# openSX70_ALADDIN_V391SEEED_20180205.net
KiCad netlist of a schematic drawn in EAGLE
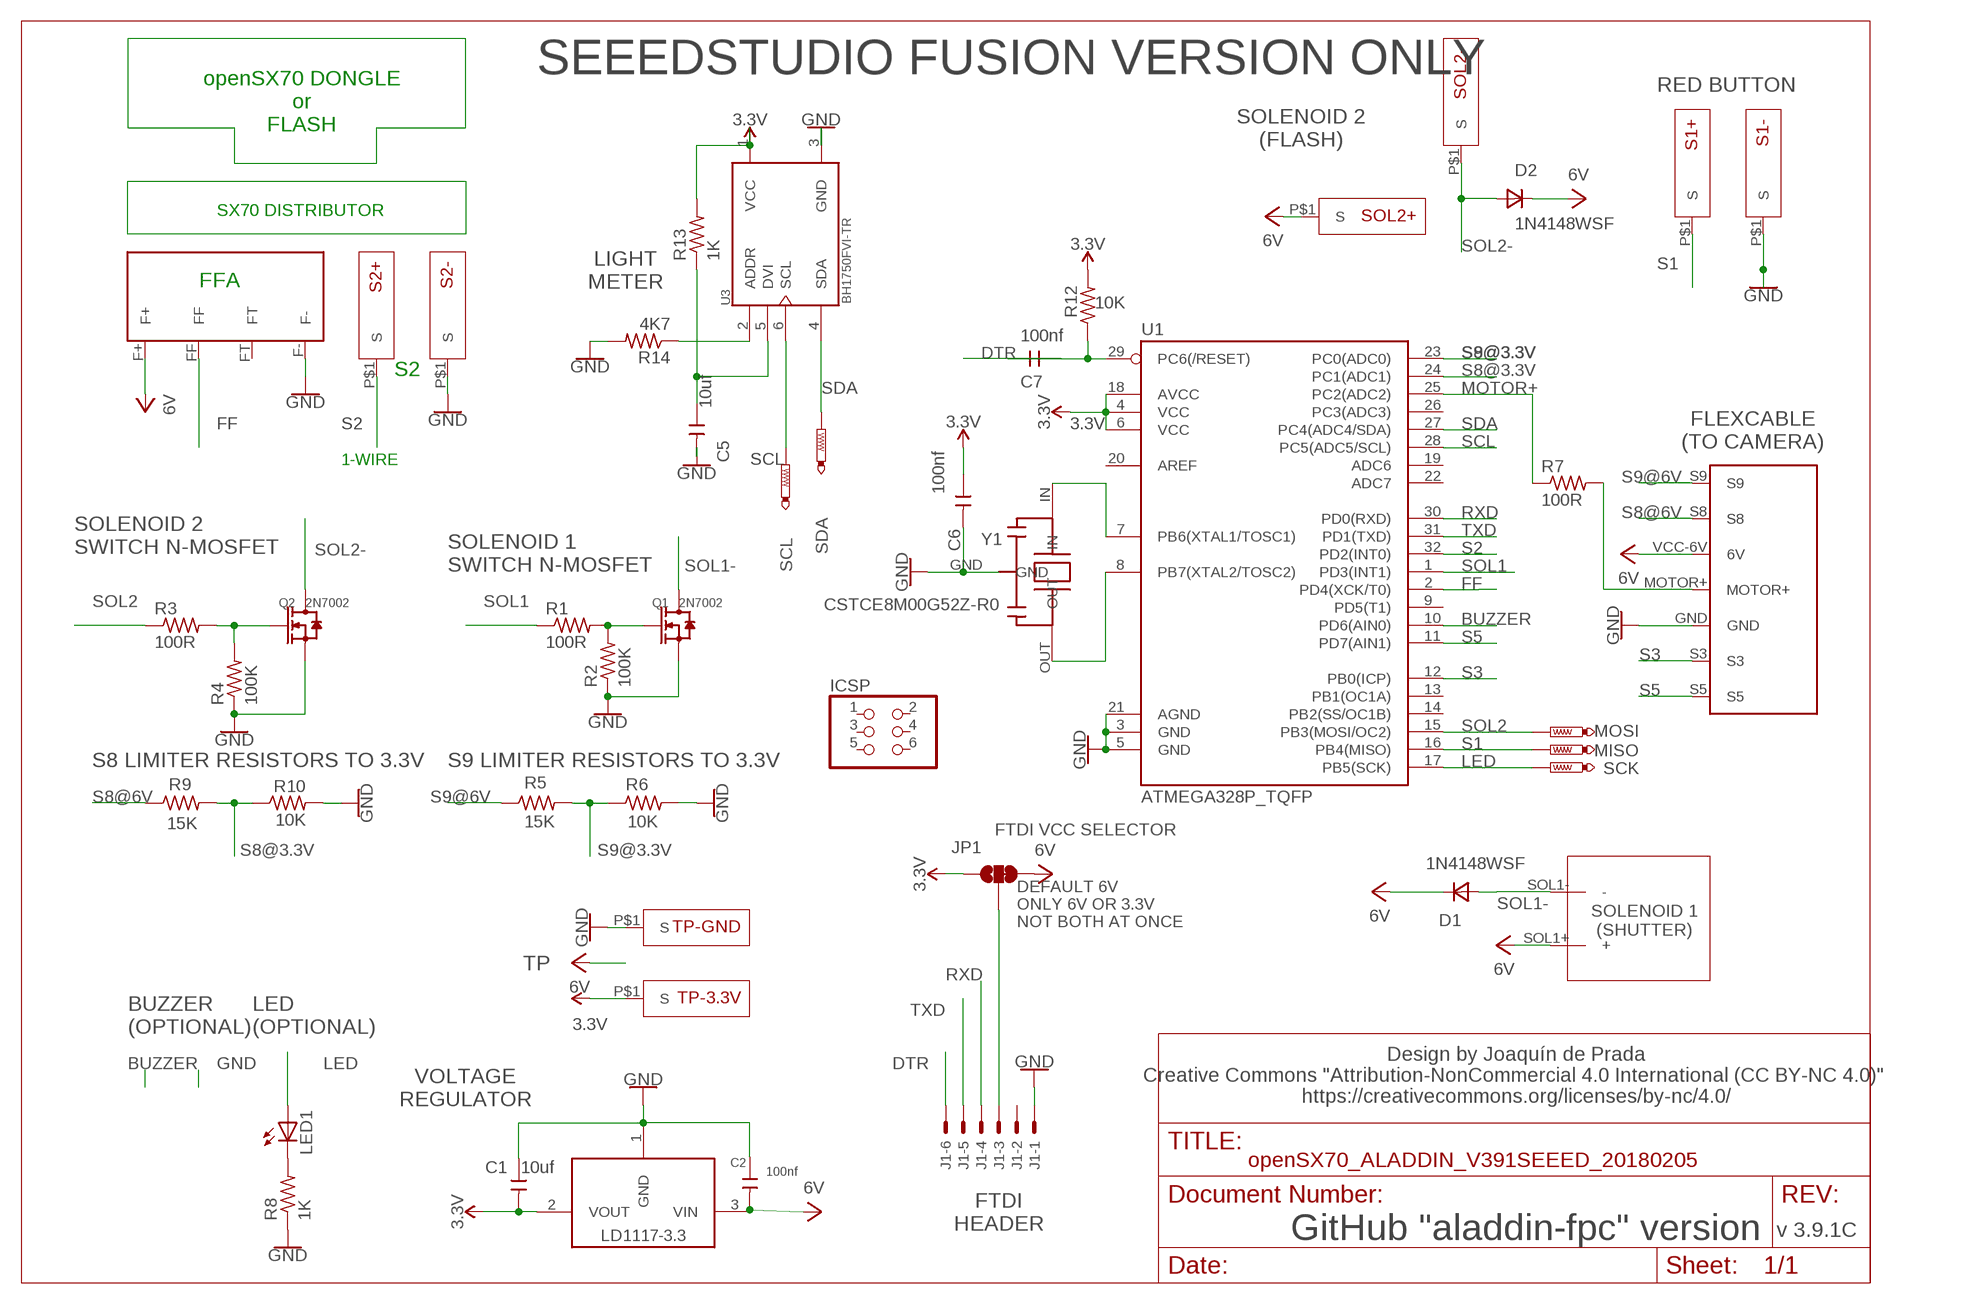
[diagram p0: schematic, sheet 1]

(export (version "E")
  (design (tool "Eeschema 10.0.6"))
  (components
    (comp (ref "C1")
      (value "10uf")
      (footprint "eagle-import:C0603")
      (fields (field (name "MPN") "CC0603KRX5R6BB106"))
      (libsource (lib "eagle-import") (part "CERAMIC-10UF-10V-10%-X5R(0603)"))
    )
    (comp (ref "C2")
      (value "100nf")
      (footprint "eagle-import:C0603")
      (fields (field (name "MPN") "CC0603KRX7R9BB104"))
      (libsource (lib "eagle-import") (part "CERAMIC-100NF-50V-10%-X7R(0603)"))
    )
    (comp (ref "C5")
      (value "10uf")
      (footprint "eagle-import:C0603")
      (fields (field (name "MPN") "CC0603KRX5R6BB106"))
      (libsource (lib "eagle-import") (part "CERAMIC-10UF-10V-10%-X5R(0603)"))
    )
    (comp (ref "C6")
      (value "100nf")
      (footprint "eagle-import:C0603")
      (fields (field (name "MPN") "CC0603KRX7R9BB104"))
      (libsource (lib "eagle-import") (part "CERAMIC-100NF-50V-10%-X7R(0603)"))
    )
    (comp (ref "C7")
      (value "100nf")
      (footprint "eagle-import:C0603")
      (fields (field (name "MPN") "CC0603KRX7R9BB104"))
      (libsource (lib "eagle-import") (part "CERAMIC-100NF-50V-10%-X7R(0603)"))
    )
    (comp (ref "D1")
      (value "1N4148WSF")
      (footprint "eagle-import:SOD323")
      (fields (field (name "MPN") "CDSOD323-T05C"))
      (libsource (lib "eagle-import") (part "DSOD323"))
    )
    (comp (ref "D2")
      (value "1N4148WSF")
      (footprint "eagle-import:SOD323")
      (fields (field (name "MPN") "CDSOD323-T05C"))
      (libsource (lib "eagle-import") (part "DSOD323"))
    )
    (comp (ref "ICSP")
      (value "PINHD-2X3")
      (footprint "eagle-import:2X03")
      (libsource (lib "eagle-import") (part "PINHD-2X3"))
    )
    (comp (ref "J1")
      (value "GND")
      (footprint "eagle-import:XF2L-0625-1")
      (fields (field (name "MF") "OMRON COMPONENTS USA") (field (name "MPN") "XF2L-0625-1"))
      (libsource (lib "eagle-import") (part "XF2-06?25-1L"))
    )
    (comp (ref "JP1")
      (value "FTDI VCC SELECTOR")
      (footprint "eagle-import:SMT-JUMPER_3_1-NC_TRACE_SILK")
      (libsource (lib "eagle-import") (part "JUMPER-SMT_3_1-NC_TRACE_SILK"))
    )
    (comp (ref "LD11172.5V")
      (value "LD1117 2.5V")
      (footprint "eagle-import:SOT223")
      (fields (field (name "MF") "Advanced Monolithic Systems") (field (name "MP") "AMS1117-5.0"))
      (libsource (lib "eagle-import") (part "LD1117-3.3"))
    )
    (comp (ref "LED1")
      (value "LEDCHIPLED_0805")
      (footprint "eagle-import:CHIPLED_0805")
      (libsource (lib "eagle-import") (part "LEDCHIPLED_0805"))
    )
    (comp (ref "MISO")
      (value "PTR1TP08R")
      (footprint "eagle-import:TP08R")
      (libsource (lib "eagle-import") (part "PTR1TP08R"))
    )
    (comp (ref "MOSI")
      (value "PTR1TP08R")
      (footprint "eagle-import:TP08R")
      (libsource (lib "eagle-import") (part "PTR1TP08R"))
    )
    (comp (ref "Q1")
      (value "2N7002")
      (footprint "eagle-import:SOT-23")
      (fields (field (name "MPN") "2N7002,215"))
      (libsource (lib "eagle-import") (part "SMD-MOSFET-N-CH-60V-300MA-LOGIC-LEVEL-FET-2N7002(SOT-23)"))
    )
    (comp (ref "Q2")
      (value "2N7002")
      (footprint "eagle-import:SOT-23")
      (fields (field (name "MPN") "2N7002,215"))
      (libsource (lib "eagle-import") (part "SMD-MOSFET-N-CH-60V-300MA-LOGIC-LEVEL-FET-2N7002(SOT-23)"))
    )
    (comp (ref "R1")
      (value "100R")
      (footprint "eagle-import:R0603")
      (libsource (lib "eagle-import") (part "R-US_R0603"))
    )
    (comp (ref "R2")
      (value "100K")
      (footprint "eagle-import:R0603")
      (libsource (lib "eagle-import") (part "R-US_R0603"))
    )
    (comp (ref "R3")
      (value "100R")
      (footprint "eagle-import:R0603")
      (libsource (lib "eagle-import") (part "R-US_R0603"))
    )
    (comp (ref "R4")
      (value "100K")
      (footprint "eagle-import:R0603")
      (libsource (lib "eagle-import") (part "R-US_R0603"))
    )
    (comp (ref "R5")
      (value "15K")
      (footprint "eagle-import:R0603")
      (libsource (lib "eagle-import") (part "R-US_R0603"))
    )
    (comp (ref "R6")
      (value "10K")
      (footprint "eagle-import:R0603")
      (libsource (lib "eagle-import") (part "R-US_R0603"))
    )
    (comp (ref "R7")
      (value "100R")
      (footprint "eagle-import:R0603")
      (libsource (lib "eagle-import") (part "R-US_R0603"))
    )
    (comp (ref "R8")
      (value "1K")
      (footprint "eagle-import:R0603")
      (libsource (lib "eagle-import") (part "R-US_R0603"))
    )
    (comp (ref "R9")
      (value "15K")
      (footprint "eagle-import:R0603")
      (libsource (lib "eagle-import") (part "R-US_R0603"))
    )
    (comp (ref "R10")
      (value "10K")
      (footprint "eagle-import:R0603")
      (libsource (lib "eagle-import") (part "R-US_R0603"))
    )
    (comp (ref "R12")
      (value "10K")
      (footprint "eagle-import:R0603")
      (libsource (lib "eagle-import") (part "R-US_R0603"))
    )
    (comp (ref "R13")
      (value "1K")
      (footprint "eagle-import:R0603")
      (libsource (lib "eagle-import") (part "R-US_R0603"))
    )
    (comp (ref "R14")
      (value "4K7")
      (footprint "eagle-import:R0603")
      (libsource (lib "eagle-import") (part "R-US_R0603"))
    )
    (comp (ref "S1+")
      (value "SX70-S-PAD-NEW")
      (footprint "eagle-import:SX70-S-PAD2")
      (libsource (lib "eagle-import") (part "SX70-S-PAD-NEW"))
    )
    (comp (ref "S1-")
      (value "SX70-S-PAD-NEW")
      (footprint "eagle-import:SX70-S-PAD2")
      (libsource (lib "eagle-import") (part "SX70-S-PAD-NEW"))
    )
    (comp (ref "S2+")
      (value "SX70-S-PAD-NEW")
      (footprint "eagle-import:SX70-S-PAD2")
      (libsource (lib "eagle-import") (part "SX70-S-PAD-NEW"))
    )
    (comp (ref "S2-")
      (value "SX70-S-PAD-NEW")
      (footprint "eagle-import:SX70-S-PAD2")
      (libsource (lib "eagle-import") (part "SX70-S-PAD-NEW"))
    )
    (comp (ref "SCK")
      (value "PTR1TP08R")
      (footprint "eagle-import:TP08R")
      (libsource (lib "eagle-import") (part "PTR1TP08R"))
    )
    (comp (ref "SCL")
      (value "PTR1TP08R")
      (footprint "eagle-import:TP08R")
      (libsource (lib "eagle-import") (part "PTR1TP08R"))
    )
    (comp (ref "SDA")
      (value "PTR1TP08R")
      (footprint "eagle-import:TP08R")
      (libsource (lib "eagle-import") (part "PTR1TP08R"))
    )
    (comp (ref "SOL1")
      (value "SX70-SOLENOID1-2PADS")
      (footprint "eagle-import:SX70-SOLENOID1-2")
      (libsource (lib "eagle-import") (part "SX70-SOLENOID1-2PADS"))
    )
    (comp (ref "SOL2+")
      (value "SX70-S-PAD-NEW")
      (footprint "eagle-import:SX70-S-PAD2")
      (libsource (lib "eagle-import") (part "SX70-S-PAD-NEW"))
    )
    (comp (ref "SOL2-")
      (value "SX70-S-PAD-NEW")
      (footprint "eagle-import:SX70-S-PAD2")
      (libsource (lib "eagle-import") (part "SX70-S-PAD-NEW"))
    )
    (comp (ref "TP-3.3V")
      (value "SX70-S-PAD-NEW")
      (footprint "eagle-import:SX70-S-PAD2")
      (libsource (lib "eagle-import") (part "SX70-S-PAD-NEW"))
    )
    (comp (ref "TP-GND")
      (value "SX70-S-PAD-NEW")
      (footprint "eagle-import:SX70-S-PAD2")
      (libsource (lib "eagle-import") (part "SX70-S-PAD-NEW"))
    )
    (comp (ref "U$1")
      (value "SX70-7-PAD")
      (footprint "eagle-import:SX70-7-PAD")
      (libsource (lib "eagle-import") (part "SX70-7-PAD"))
    )
    (comp (ref "U$2")
      (value "FFA")
      (footprint "eagle-import:FFA-PAD-PACKAGE")
      (libsource (lib "eagle-import") (part "SX70-FFA-PAD"))
    )
    (comp (ref "U1")
      (value "ATMEGA328P_TQFP")
      (footprint "eagle-import:TQFP32-08")
      (libsource (lib "eagle-import") (part "ATMEGA328P_TQFP"))
    )
    (comp (ref "U3")
      (value "BH1750FVI-TR")
      (footprint "eagle-import:SOTFL50P300X75-6N")
      (fields (field (name "MF") "Rohm"))
      (libsource (lib "eagle-import") (part "BH1750FVI-TR"))
    )
    (comp (ref "Y1")
      (value "CSTCE8M00G52Z-R0")
      (footprint "eagle-import:CFP95P160X100-3N")
      (fields (field (name "MF") "Murata") (field (name "MP") "CSTCE16M0V53-R0"))
      (libsource (lib "eagle-import") (part "CSTCE16M0V53-R0"))
    )
  )
  (nets
    (net (code "1") (name "/BUZZER") (class "Default")
      (node (ref "U1") (pin "10") (pinfunction "PD6(AIN0)_10") (pintype "bidirectional"))
    )
    (net (code "2") (name "/DTR") (class "Default")
      (node (ref "C7") (pin "1") (pinfunction "1_1") (pintype "passive"))
      (node (ref "J1") (pin "6") (pinfunction "MS_6") (pintype "passive"))
    )
    (net (code "3") (name "/FF") (class "Default")
      (node (ref "U$2") (pin "FF") (pinfunction "FF_FF") (pintype "bidirectional"))
      (node (ref "U1") (pin "2") (pinfunction "PD4(XCK/T0)_2") (pintype "bidirectional"))
    )
    (net (code "4") (name "/LED") (class "Default")
      (node (ref "LED1") (pin "A") (pinfunction "A_A") (pintype "passive"))
      (node (ref "SCK") (pin "TP") (pinfunction "TP_TP") (pintype "input"))
      (node (ref "U1") (pin "17") (pinfunction "PB5(SCK)_17") (pintype "bidirectional"))
    )
    (net (code "5") (name "/MOTOR+") (class "Default")
      (node (ref "R7") (pin "1") (pinfunction "1_1") (pintype "passive"))
      (node (ref "U1") (pin "25") (pinfunction "PC2(ADC2)_25") (pintype "bidirectional"))
    )
    (net (code "6") (name "/RXD") (class "Default")
      (node (ref "J1") (pin "4") (pinfunction "MS_4") (pintype "passive"))
      (node (ref "U1") (pin "30") (pinfunction "PD0(RXD)_30") (pintype "bidirectional"))
    )
    (net (code "7") (name "/S1") (class "Default")
      (node (ref "MISO") (pin "TP") (pinfunction "TP_TP") (pintype "input"))
      (node (ref "S1+") (pin "P$1") (pinfunction "S_P$1") (pintype "bidirectional"))
      (node (ref "U1") (pin "16") (pinfunction "PB4(MISO)_16") (pintype "bidirectional"))
    )
    (net (code "8") (name "/S2") (class "Default")
      (node (ref "S2+") (pin "P$1") (pinfunction "S_P$1") (pintype "bidirectional"))
      (node (ref "U1") (pin "32") (pinfunction "PD2(INT0)_32") (pintype "bidirectional"))
    )
    (net (code "9") (name "/S3") (class "Default")
      (node (ref "U$1") (pin "S3") (pinfunction "S3_S3") (pintype "bidirectional"))
      (node (ref "U1") (pin "12") (pinfunction "PB0(ICP)_12") (pintype "bidirectional"))
    )
    (net (code "10") (name "/S5") (class "Default")
      (node (ref "U$1") (pin "S5") (pinfunction "S5_S5") (pintype "bidirectional"))
      (node (ref "U1") (pin "11") (pinfunction "PD7(AIN1)_11") (pintype "bidirectional"))
    )
    (net (code "11") (name "/S8@3.3V") (class "Default")
      (node (ref "R10") (pin "1") (pinfunction "1_1") (pintype "passive"))
      (node (ref "R9") (pin "2") (pinfunction "2_2") (pintype "passive"))
      (node (ref "U1") (pin "24") (pinfunction "PC1(ADC1)_24") (pintype "bidirectional"))
    )
    (net (code "12") (name "/S8@6V") (class "Default")
      (node (ref "R9") (pin "1") (pinfunction "1_1") (pintype "passive"))
      (node (ref "U$1") (pin "S8") (pinfunction "S8_S8") (pintype "bidirectional"))
    )
    (net (code "13") (name "/S9@3.3V") (class "Default")
      (node (ref "R5") (pin "2") (pinfunction "2_2") (pintype "passive"))
      (node (ref "R6") (pin "1") (pinfunction "1_1") (pintype "passive"))
      (node (ref "U1") (pin "23") (pinfunction "PC0(ADC0)_23") (pintype "bidirectional"))
    )
    (net (code "14") (name "/S9@6V") (class "Default")
      (node (ref "R5") (pin "1") (pinfunction "1_1") (pintype "passive"))
      (node (ref "U$1") (pin "S9") (pinfunction "S9_S9") (pintype "bidirectional"))
    )
    (net (code "15") (name "/SCL") (class "Default")
      (node (ref "SCL") (pin "TP") (pinfunction "TP_TP") (pintype "input"))
      (node (ref "U1") (pin "28") (pinfunction "PC5(ADC5/SCL)_28") (pintype "bidirectional"))
      (node (ref "U3") (pin "6") (pinfunction "SCL_6") (pintype "input"))
    )
    (net (code "16") (name "/SDA") (class "Default")
      (node (ref "SDA") (pin "TP") (pinfunction "TP_TP") (pintype "input"))
      (node (ref "U1") (pin "27") (pinfunction "PC4(ADC4/SDA)_27") (pintype "bidirectional"))
      (node (ref "U3") (pin "4") (pinfunction "SDA_4") (pintype "bidirectional"))
    )
    (net (code "17") (name "/SOL1") (class "Default")
      (node (ref "R1") (pin "1") (pinfunction "1_1") (pintype "passive"))
      (node (ref "U1") (pin "1") (pinfunction "PD3(INT1)_1") (pintype "bidirectional"))
    )
    (net (code "18") (name "/SOL1-") (class "Default")
      (node (ref "D1") (pin "2") (pinfunction "A_2") (pintype "passive"))
      (node (ref "Q1") (pin "3") (pinfunction "D_3") (pintype "passive"))
      (node (ref "SOL1") (pin "SOL1-") (pinfunction "-_SOL1-") (pintype "bidirectional"))
    )
    (net (code "19") (name "/SOL2") (class "Default")
      (node (ref "MOSI") (pin "TP") (pinfunction "TP_TP") (pintype "input"))
      (node (ref "R3") (pin "1") (pinfunction "1_1") (pintype "passive"))
      (node (ref "U1") (pin "15") (pinfunction "PB3(MOSI/OC2)_15") (pintype "bidirectional"))
    )
    (net (code "20") (name "/SOL2-") (class "Default")
      (node (ref "D2") (pin "2") (pinfunction "A_2") (pintype "passive"))
      (node (ref "Q2") (pin "3") (pinfunction "D_3") (pintype "passive"))
      (node (ref "SOL2-") (pin "P$1") (pinfunction "S_P$1") (pintype "bidirectional"))
    )
    (net (code "21") (name "/TXD") (class "Default")
      (node (ref "J1") (pin "5") (pinfunction "MS_5") (pintype "passive"))
      (node (ref "U1") (pin "31") (pinfunction "PD1(TXD)_31") (pintype "bidirectional"))
    )
    (net (code "22") (name "3.3V") (class "Default")
      (node (ref "C1") (pin "2") (pinfunction "2_2") (pintype "passive"))
      (node (ref "C6") (pin "1") (pinfunction "1_1") (pintype "passive"))
      (node (ref "JP1") (pin "1") (pinfunction "1_1") (pintype "passive"))
      (node (ref "LD11172.5V") (pin "2") (pinfunction "VOUT_2") (pintype "bidirectional"))
      (node (ref "R12") (pin "2") (pinfunction "2_2") (pintype "passive"))
      (node (ref "R13") (pin "2") (pinfunction "2_2") (pintype "passive"))
      (node (ref "TP-3.3V") (pin "P$1") (pinfunction "S_P$1") (pintype "bidirectional"))
      (node (ref "U1") (pin "18") (pinfunction "AVCC_18") (pintype "bidirectional"))
      (node (ref "U1") (pin "4") (pinfunction "VCC_4") (pintype "bidirectional"))
      (node (ref "U1") (pin "6") (pinfunction "VCC_6") (pintype "bidirectional"))
      (node (ref "U3") (pin "1") (pinfunction "VCC_1") (pintype "power_in"))
    )
    (net (code "23") (name "6V") (class "Default")
      (node (ref "C2") (pin "2") (pinfunction "2_2") (pintype "passive"))
      (node (ref "D1") (pin "1") (pinfunction "C_1") (pintype "passive"))
      (node (ref "D2") (pin "1") (pinfunction "C_1") (pintype "passive"))
      (node (ref "JP1") (pin "3") (pinfunction "3_3") (pintype "passive"))
      (node (ref "LD11172.5V") (pin "3") (pinfunction "VIN_3") (pintype "bidirectional"))
      (node (ref "SOL1") (pin "SOL1+") (pinfunction "+_SOL1+") (pintype "bidirectional"))
      (node (ref "SOL2+") (pin "P$1") (pinfunction "S_P$1") (pintype "bidirectional"))
      (node (ref "U$1") (pin "VCC-6V") (pinfunction "6V_VCC-6V") (pintype "bidirectional"))
      (node (ref "U$2") (pin "F+") (pinfunction "F+_F+") (pintype "bidirectional"))
    )
    (net (code "24") (name "GND") (class "Default")
      (node (ref "C1") (pin "1") (pinfunction "1_1") (pintype "passive"))
      (node (ref "C2") (pin "1") (pinfunction "1_1") (pintype "passive"))
      (node (ref "C5") (pin "2") (pinfunction "2_2") (pintype "passive"))
      (node (ref "C6") (pin "2") (pinfunction "2_2") (pintype "passive"))
      (node (ref "J1") (pin "1") (pinfunction "MS_1") (pintype "passive"))
      (node (ref "LD11172.5V") (pin "1") (pinfunction "GND_1") (pintype "bidirectional"))
      (node (ref "Q1") (pin "2") (pinfunction "S_2") (pintype "passive"))
      (node (ref "Q2") (pin "2") (pinfunction "S_2") (pintype "passive"))
      (node (ref "R10") (pin "2") (pinfunction "2_2") (pintype "passive"))
      (node (ref "R14") (pin "2") (pinfunction "2_2") (pintype "passive"))
      (node (ref "R2") (pin "1") (pinfunction "1_1") (pintype "passive"))
      (node (ref "R4") (pin "1") (pinfunction "1_1") (pintype "passive"))
      (node (ref "R6") (pin "2") (pinfunction "2_2") (pintype "passive"))
      (node (ref "R8") (pin "1") (pinfunction "1_1") (pintype "passive"))
      (node (ref "S1-") (pin "P$1") (pinfunction "S_P$1") (pintype "bidirectional"))
      (node (ref "S2-") (pin "P$1") (pinfunction "S_P$1") (pintype "bidirectional"))
      (node (ref "TP-GND") (pin "P$1") (pinfunction "S_P$1") (pintype "bidirectional"))
      (node (ref "U$1") (pin "GND") (pinfunction "GND_GND") (pintype "bidirectional"))
      (node (ref "U$2") (pin "F-") (pinfunction "F-_F-") (pintype "bidirectional"))
      (node (ref "U1") (pin "21") (pinfunction "AGND_21") (pintype "bidirectional"))
      (node (ref "U1") (pin "3") (pinfunction "GND_3") (pintype "bidirectional"))
      (node (ref "U1") (pin "5") (pinfunction "GND_5") (pintype "bidirectional"))
      (node (ref "U3") (pin "3") (pinfunction "GND_3") (pintype "power_in"))
      (node (ref "Y1") (pin "GND") (pinfunction "GND_GND") (pintype "passive"))
    )
    (net (code "25") (name "Net-(J1C-MS)") (class "Default")
      (node (ref "J1") (pin "3") (pinfunction "MS_3") (pintype "passive"))
      (node (ref "JP1") (pin "2") (pinfunction "2_2") (pintype "passive"))
    )
    (net (code "26") (name "Net-(LED1-PadC)") (class "Default")
      (node (ref "LED1") (pin "C") (pinfunction "C_C") (pintype "passive"))
      (node (ref "R8") (pin "2") (pinfunction "2_2") (pintype "passive"))
    )
    (net (code "27") (name "Net-(Q1-G)") (class "Default")
      (node (ref "Q1") (pin "1") (pinfunction "G_1") (pintype "passive"))
      (node (ref "R1") (pin "2") (pinfunction "2_2") (pintype "passive"))
      (node (ref "R2") (pin "2") (pinfunction "2_2") (pintype "passive"))
    )
    (net (code "28") (name "Net-(Q2-G)") (class "Default")
      (node (ref "Q2") (pin "1") (pinfunction "G_1") (pintype "passive"))
      (node (ref "R3") (pin "2") (pinfunction "2_2") (pintype "passive"))
      (node (ref "R4") (pin "2") (pinfunction "2_2") (pintype "passive"))
    )
    (net (code "29") (name "Net-(R7-Pad2)") (class "Default")
      (node (ref "R7") (pin "2") (pinfunction "2_2") (pintype "passive"))
      (node (ref "U$1") (pin "MOTOR+") (pinfunction "MOTOR+_MOTOR+") (pintype "bidirectional"))
    )
    (net (code "30") (name "Net-(U1-PB6(XTAL1{slash}TOSC1))") (class "Default")
      (node (ref "U1") (pin "7") (pinfunction "PB6(XTAL1/TOSC1)_7") (pintype "bidirectional"))
      (node (ref "Y1") (pin "IN") (pinfunction "IN_IN") (pintype "input"))
    )
    (net (code "31") (name "Net-(U1-PB7(XTAL2{slash}TOSC2))") (class "Default")
      (node (ref "U1") (pin "8") (pinfunction "PB7(XTAL2/TOSC2)_8") (pintype "bidirectional"))
      (node (ref "Y1") (pin "OUT") (pinfunction "OUT_OUT") (pintype "output"))
    )
    (net (code "32") (name "Net-(U1-PC6({slash}RESET))") (class "Default")
      (node (ref "C7") (pin "2") (pinfunction "2_2") (pintype "passive"))
      (node (ref "R12") (pin "1") (pinfunction "1_1") (pintype "passive"))
      (node (ref "U1") (pin "29") (pinfunction "PC6(/RESET)_29") (pintype "bidirectional"))
    )
    (net (code "33") (name "Net-(U3-ADDR)") (class "Default")
      (node (ref "R14") (pin "1") (pinfunction "1_1") (pintype "passive"))
      (node (ref "U3") (pin "2") (pinfunction "ADDR_2") (pintype "input"))
    )
    (net (code "34") (name "Net-(U3-DVI)") (class "Default")
      (node (ref "C5") (pin "1") (pinfunction "1_1") (pintype "passive"))
      (node (ref "R13") (pin "1") (pinfunction "1_1") (pintype "passive"))
      (node (ref "U3") (pin "5") (pinfunction "DVI_5") (pintype "input"))
    )
    (net (code "35") (name "unconnected-(ICSP-Pad1)") (class "Default")
      (node (ref "ICSP") (pin "1") (pinfunction "1_1") (pintype "passive"))
    )
    (net (code "36") (name "unconnected-(ICSP-Pad2)") (class "Default")
      (node (ref "ICSP") (pin "2") (pinfunction "2_2") (pintype "passive"))
    )
    (net (code "37") (name "unconnected-(ICSP-Pad3)") (class "Default")
      (node (ref "ICSP") (pin "3") (pinfunction "3_3") (pintype "passive"))
    )
    (net (code "38") (name "unconnected-(ICSP-Pad4)") (class "Default")
      (node (ref "ICSP") (pin "4") (pinfunction "4_4") (pintype "passive"))
    )
    (net (code "39") (name "unconnected-(ICSP-Pad5)") (class "Default")
      (node (ref "ICSP") (pin "5") (pinfunction "5_5") (pintype "passive"))
    )
    (net (code "40") (name "unconnected-(ICSP-Pad6)") (class "Default")
      (node (ref "ICSP") (pin "6") (pinfunction "6_6") (pintype "passive"))
    )
    (net (code "41") (name "unconnected-(J1B-MS-Pad2)") (class "Default")
      (node (ref "J1") (pin "2") (pinfunction "MS_2") (pintype "passive"))
    )
    (net (code "42") (name "unconnected-(U$2-PadFT)") (class "Default")
      (node (ref "U$2") (pin "FT") (pinfunction "FT_FT") (pintype "bidirectional"))
    )
    (net (code "43") (name "unconnected-(U1-ADC6-Pad19)") (class "Default")
      (node (ref "U1") (pin "19") (pinfunction "ADC6_19") (pintype "bidirectional"))
    )
    (net (code "44") (name "unconnected-(U1-ADC7-Pad22)") (class "Default")
      (node (ref "U1") (pin "22") (pinfunction "ADC7_22") (pintype "bidirectional"))
    )
    (net (code "45") (name "unconnected-(U1-AREF-Pad20)") (class "Default")
      (node (ref "U1") (pin "20") (pinfunction "AREF_20") (pintype "bidirectional"))
    )
    (net (code "46") (name "unconnected-(U1-PB1(OC1A)-Pad13)") (class "Default")
      (node (ref "U1") (pin "13") (pinfunction "PB1(OC1A)_13") (pintype "bidirectional"))
    )
    (net (code "47") (name "unconnected-(U1-PB2(SS{slash}OC1B)-Pad14)") (class "Default")
      (node (ref "U1") (pin "14") (pinfunction "PB2(SS/OC1B)_14") (pintype "bidirectional"))
    )
    (net (code "48") (name "unconnected-(U1-PC3(ADC3)-Pad26)") (class "Default")
      (node (ref "U1") (pin "26") (pinfunction "PC3(ADC3)_26") (pintype "bidirectional"))
    )
    (net (code "49") (name "unconnected-(U1-PD5(T1)-Pad9)") (class "Default")
      (node (ref "U1") (pin "9") (pinfunction "PD5(T1)_9") (pintype "bidirectional"))
    )
  )
)
